# Power_LDO_5V.net
KiCad netlist of a schematic drawn in Altium Designer
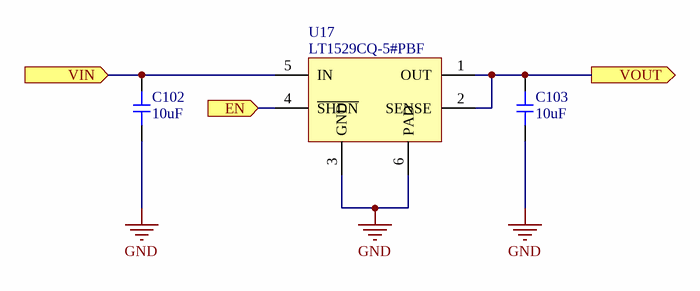
[diagram p0: Power_LDO_5V.SchDoc]

(export (version "E")
  (design (tool "Eeschema 10.0.6"))
  (components
    (comp (ref "C102")
      (value "10uF")
      (footprint "0603-CAP")
      (description "Capacitor")
      (libsource (lib "AMDC") (part "Capacitor"))
    )
    (comp (ref "C103")
      (value "10uF")
      (footprint "0603-CAP")
      (description "Capacitor")
      (libsource (lib "AMDC") (part "Capacitor"))
    )
    (comp (ref "U17")
      (value "LT1529CQ-5#PBF")
      (footprint "5-DDPAK")
      (description "IC REG LINEAR 5V 3A 5DDPAK")
      (libsource (lib "AMDC") (part "LT1529CQ-5#PBF"))
    )
  )
  (nets
    (net (code "1") (name "/EN") (class "Default")
      (node (ref "U17") (pin "4") (pinfunction "~{SHDN}_4") (pintype "passive"))
    )
    (net (code "2") (name "/VIN") (class "Default")
      (node (ref "C102") (pin "1") (pinfunction "1_1") (pintype "passive"))
      (node (ref "U17") (pin "5") (pinfunction "IN_5") (pintype "passive"))
    )
    (net (code "3") (name "/VOUT") (class "Default")
      (node (ref "C103") (pin "1") (pinfunction "1_1") (pintype "passive"))
      (node (ref "U17") (pin "1") (pinfunction "OUT_1") (pintype "passive"))
      (node (ref "U17") (pin "2") (pinfunction "SENSE_2") (pintype "passive"))
    )
    (net (code "4") (name "GND") (class "Default")
      (node (ref "C102") (pin "2") (pinfunction "2_2") (pintype "passive"))
      (node (ref "C103") (pin "2") (pinfunction "2_2") (pintype "passive"))
      (node (ref "U17") (pin "3") (pinfunction "GND_3") (pintype "passive"))
      (node (ref "U17") (pin "6") (pinfunction "PAD_6") (pintype "passive"))
    )
  )
)
